# Passive-buzzer-module_2025-10-18.net
KiCad netlist of a schematic drawn in Altium Designer
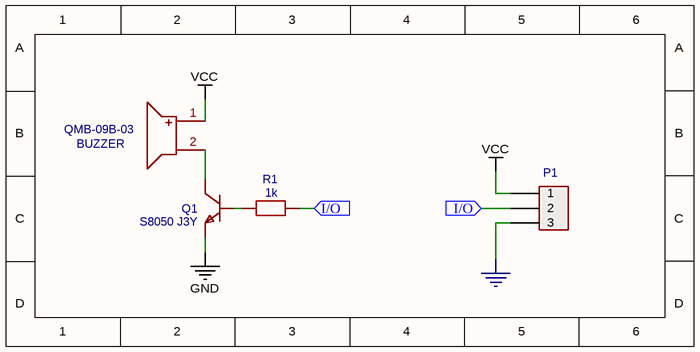
[diagram p0: Passive-buzzer-module_2025-10-18.schdoc]

(export (version "E")
  (design (tool "Eeschema 10.0.6"))
  (components
    (comp (ref "BUZZER")
      (value "QMB-09B-03")
      (fields (field (name "MANUFACTURER") "华能") (field (name "CONTRIBUTOR") "LCSC"))
      (libsource (lib "altium-import") (part "root_0_QMB-09B-03_"))
    )
    (comp (ref "P1")
      (value "Header-Male-2.54_1x3")
      (fields (field (name "MANUFACTURER") "LCSC"))
      (libsource (lib "altium-import") (part "root_2_Header-Male-2.54_1x3_"))
    )
    (comp (ref "Q1")
      (value "S8050 J3Y")
      (fields
        (field (name "MANUFACTURER") "集晶电子")
        (field (name "MANUFACTURER PART") "S8050")
        (field (name "CONTRIBUTOR") "LCSC")
      )
      (libsource (lib "altium-import") (part "root_0_S8050 J3Y_"))
    )
    (comp (ref "R1")
      (value "1k")
      (fields (field (name "CONTRIBUTOR") "LCEDA_Lib"))
      (libsource (lib "altium-import") (part "root_0_1k_"))
    )
  )
  (nets
    (net (code "1") (name "/I{slash}O") (class "Default")
      (node (ref "P1") (pin "2") (pinfunction "2_2") (pintype "passive"))
      (node (ref "R1") (pin "1") (pinfunction "1_1") (pintype "passive"))
    )
    (net (code "2") (name "GND") (class "Default")
      (node (ref "P1") (pin "3") (pinfunction "3_3") (pintype "passive"))
      (node (ref "Q1") (pin "2") (pinfunction "E_2") (pintype "passive"))
    )
    (net (code "3") (name "Net-(Q1-B)") (class "Default")
      (node (ref "Q1") (pin "1") (pinfunction "B_1") (pintype "passive"))
      (node (ref "R1") (pin "2") (pinfunction "2_2") (pintype "passive"))
    )
    (net (code "4") (name "Net-(Q1-C)") (class "Default")
      (node (ref "BUZZER") (pin "2") (pinfunction "2_2") (pintype "passive"))
      (node (ref "Q1") (pin "3") (pinfunction "C_3") (pintype "passive"))
    )
    (net (code "5") (name "VCC") (class "Default")
      (node (ref "BUZZER") (pin "1") (pinfunction "1_1") (pintype "passive"))
      (node (ref "P1") (pin "1") (pinfunction "1_1") (pintype "passive"))
    )
  )
)
